# 2016_AdvBeacon.net
KiCad netlist of a schematic drawn in Altium Designer
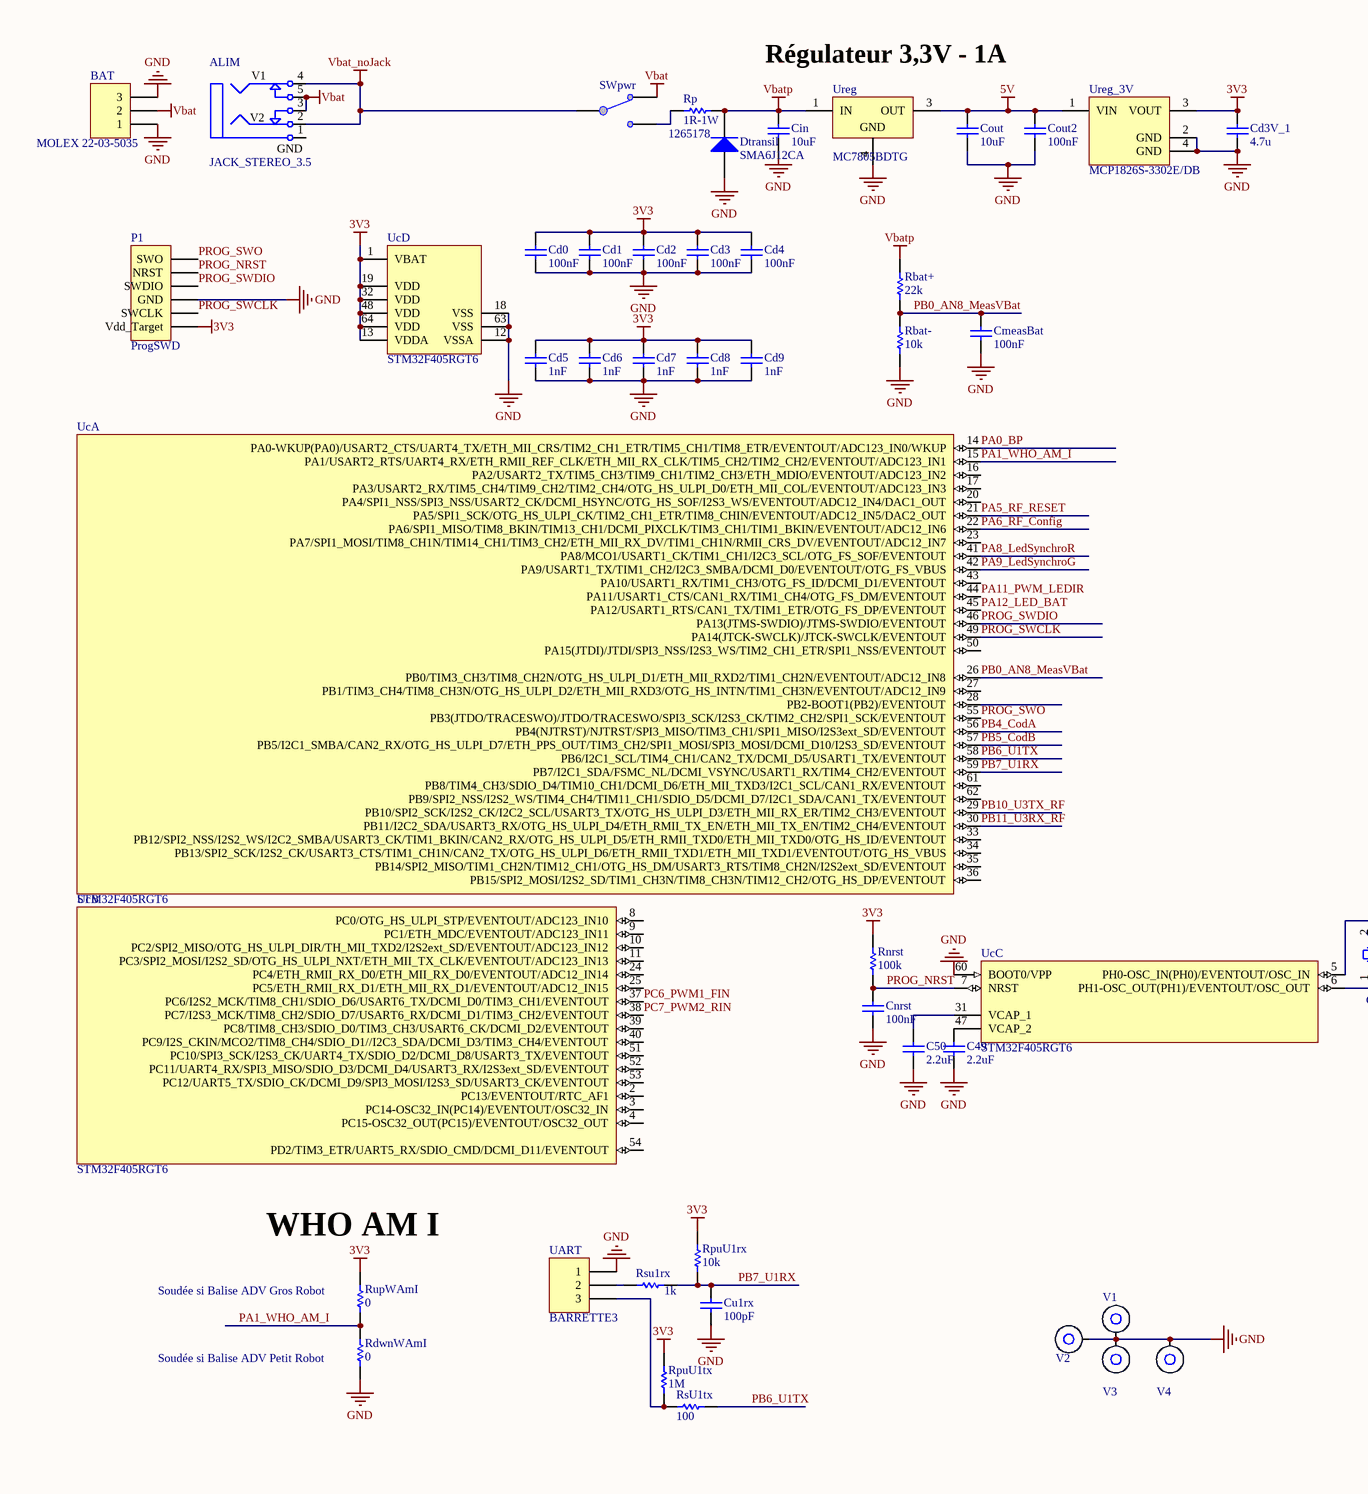
[diagram p0: 2016_AdvBeacon.SchDoc, left]
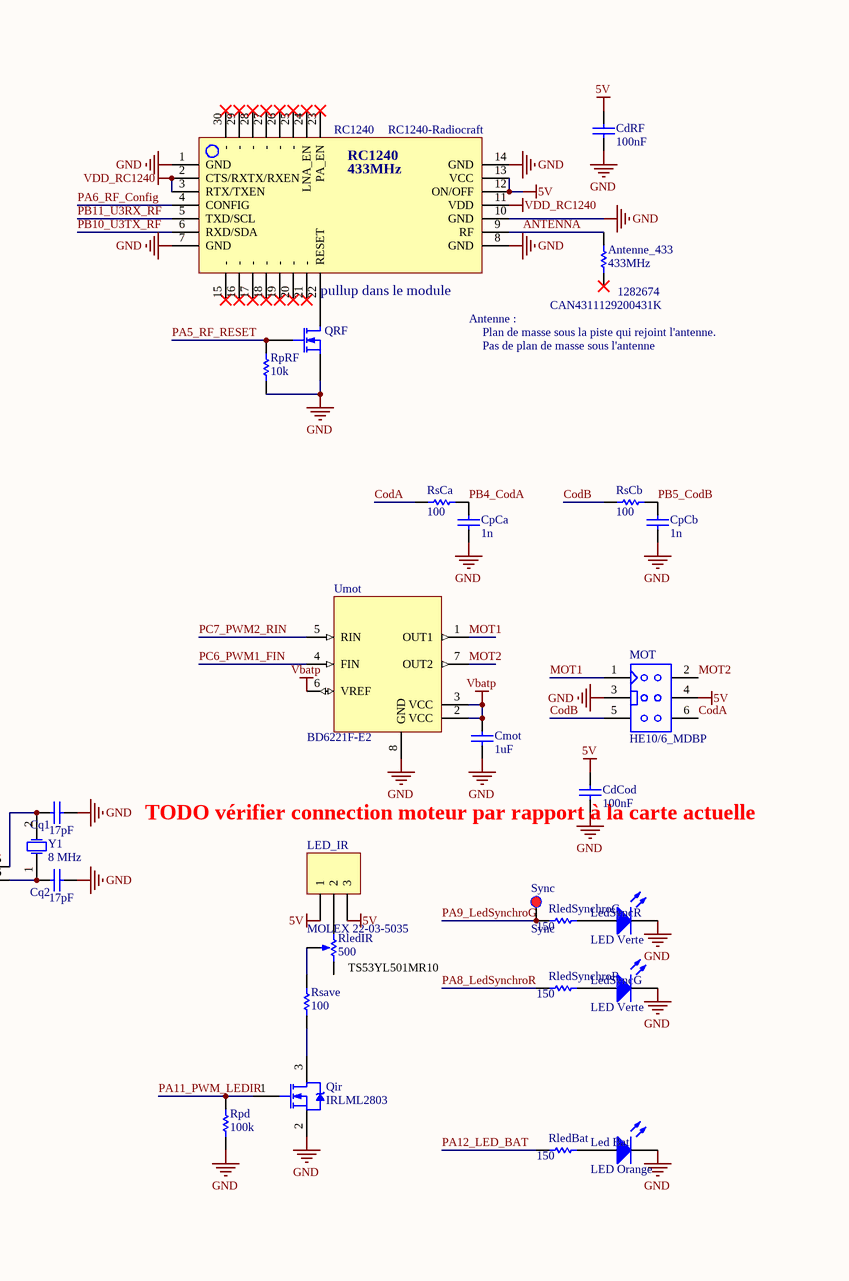
[diagram p1: 2016_AdvBeacon.SchDoc, middle]
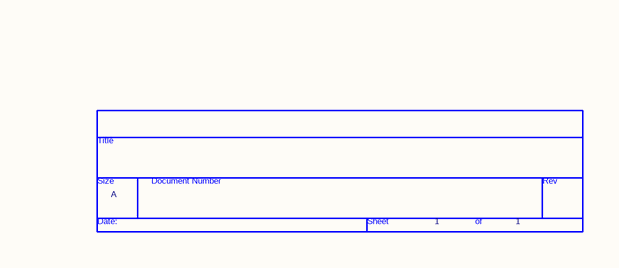
[diagram p2: 2016_AdvBeacon.SchDoc, right]

(export (version "E")
  (design (tool "Eeschema 10.0.6"))
  (components
    (comp (ref "*")
      (value "TitleBlock0")
      (fields (field (name "PAGE COUNT") "1") (field (name "PAGE NUMBER") "1") (field (name "PAGE SIZE") "A"))
      (libsource (lib "*") (part "TitleBlock0"))
    )
    (comp (ref "ALIM")
      (value "EMBASE_JACK_STEREO_3.5mm")
      (footprint "EMBASE_JACK_STEREO_3.5 mm")
      (description "EMBASE JACK STEREO 3.5mm")
      (fields (field (name "TYPE") "JACK_STEREO_3.5"))
      (libsource (lib "connecteurs") (part "EMBASE_JACK_STEREO_3.5mm"))
    )
    (comp (ref "Antenne_433")
      (value "433MHz")
      (footprint "R1206_N")
      (description "CAN4311129200431K")
      (fields
        (field (name "PACKAGEREFERENCE") "CAN4311129200431K")
        (field (name "FAR") "1282674")
        (field (name "PUBLISHER") "Altium Limited")
      )
      (libsource (lib "_ROBOT") (part "Resistor"))
    )
    (comp (ref "BAT")
      (value "MOLEX 22-03-5035")
      (footprint "MOLEX3_2.5MM")
      (description "Header, 3-Pin")
      (fields (field (name "PUBLISHER") "Altium Limited"))
      (libsource (lib "") (part "BARRETTE3_1"))
    )
    (comp (ref "C49")
      (value "2.2uF")
      (footprint "C0805_N")
      (description "Capacitor")
      (fields (field (name "PUBLISHER") "Altium Limited"))
      (libsource (lib "_ROBOT") (part "Condensateur"))
    )
    (comp (ref "C50")
      (value "2.2uF")
      (footprint "C0805_N")
      (description "Capacitor")
      (fields (field (name "PUBLISHER") "Altium Limited"))
      (libsource (lib "_ROBOT") (part "Condensateur"))
    )
    (comp (ref "Cd0")
      (value "100nF")
      (footprint "C0805_N")
      (description "Capacitor")
      (fields (field (name "PUBLISHER") "Altium Limited"))
      (libsource (lib "_ROBOT") (part "Condensateur"))
    )
    (comp (ref "Cd1")
      (value "100nF")
      (footprint "C0805_N")
      (description "Capacitor")
      (fields (field (name "PUBLISHER") "Altium Limited"))
      (libsource (lib "_ROBOT") (part "Condensateur"))
    )
    (comp (ref "Cd2")
      (value "100nF")
      (footprint "C0805_N")
      (description "Capacitor")
      (fields (field (name "PUBLISHER") "Altium Limited"))
      (libsource (lib "_ROBOT") (part "Condensateur"))
    )
    (comp (ref "Cd3")
      (value "100nF")
      (footprint "C0805_N")
      (description "Capacitor")
      (fields (field (name "PUBLISHER") "Altium Limited"))
      (libsource (lib "_ROBOT") (part "Condensateur"))
    )
    (comp (ref "Cd3V_1")
      (value "4.7u")
      (footprint "C0805_N")
      (description "Capacitor")
      (fields (field (name "PUBLISHER") "Altium Limited"))
      (libsource (lib "DG_Condensateur") (part "Capacitor"))
    )
    (comp (ref "Cd4")
      (value "100nF")
      (footprint "C0805_N")
      (description "Capacitor")
      (fields (field (name "PUBLISHER") "Altium Limited"))
      (libsource (lib "_ROBOT") (part "Condensateur"))
    )
    (comp (ref "Cd5")
      (value "1nF")
      (footprint "C0805_N")
      (description "Capacitor")
      (fields (field (name "PUBLISHER") "Altium Limited"))
      (libsource (lib "_ROBOT") (part "Condensateur"))
    )
    (comp (ref "Cd6")
      (value "1nF")
      (footprint "C0805_N")
      (description "Capacitor")
      (fields (field (name "PUBLISHER") "Altium Limited"))
      (libsource (lib "_ROBOT") (part "Condensateur"))
    )
    (comp (ref "Cd7")
      (value "1nF")
      (footprint "C0805_N")
      (description "Capacitor")
      (fields (field (name "PUBLISHER") "Altium Limited"))
      (libsource (lib "_ROBOT") (part "Condensateur"))
    )
    (comp (ref "Cd8")
      (value "1nF")
      (footprint "C0805_N")
      (description "Capacitor")
      (fields (field (name "PUBLISHER") "Altium Limited"))
      (libsource (lib "_ROBOT") (part "Condensateur"))
    )
    (comp (ref "Cd9")
      (value "1nF")
      (footprint "C0805_N")
      (description "Capacitor")
      (fields (field (name "PUBLISHER") "Altium Limited"))
      (libsource (lib "_ROBOT") (part "Condensateur"))
    )
    (comp (ref "CdCod")
      (value "100nF")
      (footprint "C0805_N")
      (description "Capacitor")
      (fields (field (name "PUBLISHER") "Altium Limited"))
      (libsource (lib "DG_Condensateur") (part "Capacitor"))
    )
    (comp (ref "CdRF")
      (value "100nF")
      (footprint "C0805_N")
      (description "Capacitor")
      (fields (field (name "PUBLISHER") "Altium Limited"))
      (libsource (lib "DG_Condensateur") (part "Capacitor"))
    )
    (comp (ref "Cin")
      (value "10uF")
      (footprint "C1206_N")
      (description "Capacitor")
      (fields (field (name "PUBLISHER") "Altium Limited"))
      (libsource (lib "DG_Condensateur") (part "Capacitor"))
    )
    (comp (ref "CmeasBat")
      (value "100nF")
      (footprint "C0805_N")
      (description "Capacitor")
      (fields (field (name "PUBLISHER") "Altium Limited"))
      (libsource (lib "DG_Condensateur") (part "Capacitor"))
    )
    (comp (ref "Cmot")
      (value "1uF")
      (footprint "C1206_N")
      (description "Capacitor")
      (fields (field (name "PUBLISHER") "Altium Limited"))
      (libsource (lib "_ROBOT") (part "Condensateur"))
    )
    (comp (ref "Cnrst")
      (value "100nF")
      (footprint "C0805_N")
      (description "Capacitor")
      (fields (field (name "PUBLISHER") "Altium Limited"))
      (libsource (lib "_ROBOT") (part "Condensateur"))
    )
    (comp (ref "Cout")
      (value "10uF")
      (footprint "C1206_N")
      (description "Capacitor")
      (fields (field (name "PUBLISHER") "Altium Limited"))
      (libsource (lib "DG_Condensateur") (part "Capacitor"))
    )
    (comp (ref "Cout2")
      (value "100nF")
      (footprint "C0805_N")
      (description "Capacitor")
      (fields (field (name "PUBLISHER") "Altium Limited"))
      (libsource (lib "DG_Condensateur") (part "Capacitor"))
    )
    (comp (ref "CpCa")
      (value "1n")
      (footprint "C0805_N")
      (description "Capacitor")
      (fields (field (name "PUBLISHER") "Altium Limited"))
      (libsource (lib "_ROBOT") (part "Condensateur"))
    )
    (comp (ref "CpCb")
      (value "1n")
      (footprint "C0805_N")
      (description "Capacitor")
      (fields (field (name "PUBLISHER") "Altium Limited"))
      (libsource (lib "_ROBOT") (part "Condensateur"))
    )
    (comp (ref "Cq1")
      (value "17pF")
      (footprint "C0805_N")
      (description "Capacitor")
      (fields (field (name "PUBLISHER") "Altium Limited"))
      (libsource (lib "_ROBOT") (part "Condensateur"))
    )
    (comp (ref "Cq2")
      (value "17pF")
      (footprint "C0805_N")
      (description "Capacitor")
      (fields (field (name "PUBLISHER") "Altium Limited"))
      (libsource (lib "_ROBOT") (part "Condensateur"))
    )
    (comp (ref "Cu1rx")
      (value "100pF")
      (footprint "C0805_N")
      (description "Capacitor")
      (fields (field (name "PUBLISHER") "Altium Limited"))
      (libsource (lib "_ROBOT") (part "Condensateur"))
    )
    (comp (ref "Dtransil")
      (value "SMA6J12CA")
      (footprint "DO214AC")
      (description "1 Amp General Purpose Rectifier")
      (fields (field (name "PUBLISHER") "Altium Limited"))
      (libsource (lib "Miscellaneous Devices") (part "Diode 1N4001"))
    )
    (comp (ref "Led Bat")
      (value "LED Orange")
      (footprint "LED_sideView_1204")
      (description "Typical LED")
      (fields (field (name "PUBLISHER") "Altium Limited"))
      (libsource (lib "DG_LED") (part "LED"))
    )
    (comp (ref "LedSyncG")
      (value "LED Verte")
      (footprint "LED_sideView_1204")
      (description "Typical LED")
      (fields (field (name "PUBLISHER") "Altium Limited"))
      (libsource (lib "DG_LED") (part "LED"))
    )
    (comp (ref "LedSyncR")
      (value "LED Verte")
      (footprint "LED_sideView_1204")
      (description "Typical LED")
      (fields (field (name "PUBLISHER") "Altium Limited"))
      (libsource (lib "DG_LED") (part "LED"))
    )
    (comp (ref "LED_IR")
      (value "MOLEX 22-03-5035")
      (footprint "MOLEX3_2.5MM")
      (description "Header, 3-Pin")
      (fields (field (name "PUBLISHER") "Altium Limited"))
      (libsource (lib "") (part "BARRETTE3_2"))
    )
    (comp (ref "MOT")
      (value "HE10/6_MALE_DROIT_BAS PROFIL")
      (footprint "HE10/6_M_D_BP")
      (description "EMBASE HE10/6 MALE DROIT BAS PROFIL")
      (fields (field (name "TYPE") "HE10/6_MDBP"))
      (libsource (lib "connecteurs") (part "HE10/6_MALE_DROIT_BAS PROFIL"))
    )
    (comp (ref "P1")
      (value "ProgSWD")
      (footprint "HDR1X6")
      (description "Header, 6-Pin")
      (fields (field (name "PUBLISHER") "Altium Limited"))
      (libsource (lib "DG_Connecteur") (part "Header 6"))
    )
    (comp (ref "Qir")
      (value "IRLML2803")
      (footprint "SOT23_N")
      (description "HEXFET Power MOSFET")
      (fields (field (name "PUBLISHER") "Altium Limited"))
      (libsource (lib "IR Discrete MOSFET - Power") (part "IRLML2803"))
    )
    (comp (ref "QRF")
      (value "Transistor MOSFET-N")
      (footprint "SOT23-3N")
      (description "N-Channel MOSFET")
      (fields (field (name "PUBLISHER") "Altium Limited"))
      (libsource (lib "_ROBOT") (part "Transistor MOSFET-N"))
    )
    (comp (ref "Rbat+")
      (value "22k")
      (footprint "R1206_N")
      (description "Resistor")
      (fields (field (name "PUBLISHER") "Altium Limited"))
      (libsource (lib "_ROBOT") (part "Resistor"))
    )
    (comp (ref "Rbat-")
      (value "10k")
      (footprint "R1206_N")
      (description "Resistor")
      (fields (field (name "PUBLISHER") "Altium Limited"))
      (libsource (lib "_ROBOT") (part "Resistor"))
    )
    (comp (ref "RC1240")
      (value "RC1240-Radiocraft")
      (footprint "RC1240")
      (description "RC1240 - Radiocraft 433MHz Transceiver")
      (libsource (lib "_ROBOT") (part "RC1240-Radiocraft"))
    )
    (comp (ref "RdwnWAmI")
      (value "0")
      (footprint "R1206_N")
      (description "Resistor")
      (fields (field (name "PUBLISHER") "Altium Limited"))
      (libsource (lib "_ROBOT") (part "Resistor"))
    )
    (comp (ref "RledBat")
      (value "150")
      (footprint "R1206_N")
      (description "Resistor")
      (fields (field (name "PUBLISHER") "Altium Limited"))
      (libsource (lib "_ROBOT") (part "Resistor"))
    )
    (comp (ref "RledIR")
      (value "500")
      (footprint "TRIMMER_CMS_TS53YL")
      (description "Trimmer monotour, Bourns,serie 3314P")
      (libsource (lib "DG_Resistance") (part "Trimmer monotour, Bourns,serie 3314P"))
    )
    (comp (ref "RledSynchroG")
      (value "150")
      (footprint "R1206_N")
      (description "Resistor")
      (fields (field (name "PUBLISHER") "Altium Limited"))
      (libsource (lib "_ROBOT") (part "Resistor"))
    )
    (comp (ref "RledSynchroR")
      (value "150")
      (footprint "R1206_N")
      (description "Resistor")
      (fields (field (name "PUBLISHER") "Altium Limited"))
      (libsource (lib "_ROBOT") (part "Resistor"))
    )
    (comp (ref "Rnrst")
      (value "100k")
      (footprint "R1206_N")
      (description "Resistor")
      (fields (field (name "PUBLISHER") "Altium Limited"))
      (libsource (lib "_ROBOT") (part "Resistor"))
    )
    (comp (ref "Rp")
      (value "1R-1W")
      (footprint "INDUCTANCE_CMS_1812")
      (description "Resistor")
      (fields (field (name "FAR") "1265178") (field (name "PUBLISHER") "Altium Limited"))
      (libsource (lib "_ROBOT") (part "Resistor"))
    )
    (comp (ref "Rpd")
      (value "100k")
      (footprint "R1206_N")
      (description "Resistor")
      (fields (field (name "PUBLISHER") "Altium Limited"))
      (libsource (lib "_ROBOT") (part "Resistor"))
    )
    (comp (ref "RpRF")
      (value "10k")
      (footprint "R1206_N")
      (description "Resistor")
      (fields (field (name "PUBLISHER") "Altium Limited"))
      (libsource (lib "_ROBOT") (part "Resistor"))
    )
    (comp (ref "RpuU1rx")
      (value "10k")
      (footprint "R1206_N")
      (description "Resistor")
      (fields (field (name "PUBLISHER") "Altium Limited"))
      (libsource (lib "_ROBOT") (part "Resistor"))
    )
    (comp (ref "RpuU1tx")
      (value "1M")
      (footprint "R1206_N")
      (description "Resistor")
      (fields (field (name "PUBLISHER") "Altium Limited"))
      (libsource (lib "_ROBOT") (part "Resistor"))
    )
    (comp (ref "Rsave")
      (value "100")
      (footprint "R1206_N")
      (description "Resistor")
      (fields (field (name "PUBLISHER") "Altium Limited"))
      (libsource (lib "_ROBOT") (part "Resistor"))
    )
    (comp (ref "RsCa")
      (value "100")
      (footprint "R1206_N")
      (description "Resistor")
      (fields (field (name "PUBLISHER") "Altium Limited"))
      (libsource (lib "_ROBOT") (part "Resistor"))
    )
    (comp (ref "RsCb")
      (value "100")
      (footprint "R1206_N")
      (description "Resistor")
      (fields (field (name "PUBLISHER") "Altium Limited"))
      (libsource (lib "_ROBOT") (part "Resistor"))
    )
    (comp (ref "Rsu1rx")
      (value "1k")
      (footprint "R1206_N")
      (description "Resistor")
      (fields (field (name "PUBLISHER") "Altium Limited"))
      (libsource (lib "_ROBOT") (part "Resistor"))
    )
    (comp (ref "RsU1tx")
      (value "100")
      (footprint "R1206_N")
      (description "Resistor")
      (fields (field (name "PUBLISHER") "Altium Limited"))
      (libsource (lib "_ROBOT") (part "Resistor"))
    )
    (comp (ref "RupWAmI")
      (value "0")
      (footprint "R1206_N")
      (description "Resistor")
      (fields (field (name "PUBLISHER") "Altium Limited"))
      (libsource (lib "_ROBOT") (part "Resistor"))
    )
    (comp (ref "SWpwr")
      (value "SW SPDT- APEM Série 523x")
      (footprint "SW_UNIPOL_DROIT - Ebay - SPDT - 11x6x5")
      (description "Switch unipolaire a levier")
      (libsource (lib "_ROBOT") (part "SW SPDT- APEM Série 523x"))
    )
    (comp (ref "Sync")
      (value "Sync")
      (footprint "Point Test_D0.9_P0.5mm")
      (description "Point test")
      (fields (field (name "PUBLISHER") "Damien GUITTON"))
      (libsource (lib "Connecteur") (part "Point Test"))
    )
    (comp (ref "UART")
      (value "BARRETTE3")
      (footprint "HDR1X3")
      (description "Header, 3-Pin")
      (fields (field (name "PUBLISHER") "Altium Limited"))
      (libsource (lib "Connecteur") (part "BARRETTE3"))
    )
    (comp (ref "Uc")
      (value "STM32F405RGT6")
      (footprint "TQFP64_V")
      (libsource (lib "STMicroelectronics+STM32+F4") (part "STM32F405RGT6"))
    )
    (comp (ref "Umot")
      (value "BD6221F-E2")
      (footprint "SO8_N")
      (description "H Bridge - 2A")
      (libsource (lib "Circuit intégré") (part "BD6220F"))
    )
    (comp (ref "Ureg")
      (value "MC7805BDTG")
      (footprint "369A-13")
      (description "Three-Terminal Positive Voltage Regulator")
      (fields (field (name "PUBLISHER") "Altium Limited"))
      (libsource (lib "ON Semi Power Mgt Voltage Regulator") (part "MC7805ACD2T"))
    )
    (comp (ref "Ureg_3V")
      (value "MCP1826S-3302E/DB")
      (footprint "SOT223-4N")
      (description "1000 mA, Low Voltage, Low Quiescent Current LDO Regulator, 3-Pin SOT-223, Extended Temperature")
      (fields (field (name "PUBLISHER") "Altium Limited"))
      (libsource (lib "Microchip Power Mgt Line Regulator") (part "MCP1826S-3302E/DB"))
    )
    (comp (ref "V1")
      (value "Entretoise WURTH CMS")
      (footprint "ENTRETOISE_CMS_DOUBLE")
      (description "Entretoise Wurth")
      (fields (field (name "PUBLISHER") "Damien Guitton"))
      (libsource (lib "_ROBOT") (part "Entretoise WURTH CMS_DOUBLE"))
    )
    (comp (ref "V2")
      (value "Entretoise WURTH CMS")
      (footprint "ENTRETOISE_CMS_DOUBLE")
      (description "Entretoise Wurth")
      (fields (field (name "PUBLISHER") "Damien Guitton"))
      (libsource (lib "_ROBOT") (part "Entretoise WURTH CMS_DOUBLE"))
    )
    (comp (ref "V3")
      (value "Entretoise WURTH CMS")
      (footprint "ENTRETOISE_CMS_DOUBLE")
      (description "Entretoise Wurth")
      (fields (field (name "PUBLISHER") "Damien Guitton"))
      (libsource (lib "_ROBOT") (part "Entretoise WURTH CMS_DOUBLE"))
    )
    (comp (ref "V4")
      (value "Entretoise WURTH CMS")
      (footprint "ENTRETOISE_CMS_DOUBLE")
      (description "Entretoise Wurth")
      (fields (field (name "PUBLISHER") "Damien Guitton"))
      (libsource (lib "_ROBOT") (part "Entretoise WURTH CMS_DOUBLE"))
    )
    (comp (ref "Y1")
      (value "8 MHz")
      (footprint "HC49/4H_SMX")
      (description "Crystal Oscillator")
      (fields (field (name "PUBLISHER") "Altium Limited"))
      (libsource (lib "_ROBOT") (part "Quartz"))
    )
  )
  (nets
    (net (code "1") (name "/ANTENNA") (class "Default")
      (node (ref "Antenne_433") (pin "1") (pinfunction "1_1") (pintype "passive"))
      (node (ref "RC1240") (pin "9") (pinfunction "RF_9") (pintype "passive"))
    )
    (net (code "2") (name "/CodA") (class "Default")
      (node (ref "MOT") (pin "6") (pinfunction "6_6") (pintype "passive"))
      (node (ref "RsCa") (pin "2") (pinfunction "2_2") (pintype "passive"))
    )
    (net (code "3") (name "/CodB") (class "Default")
      (node (ref "MOT") (pin "5") (pinfunction "5_5") (pintype "passive"))
      (node (ref "RsCb") (pin "2") (pinfunction "2_2") (pintype "passive"))
    )
    (net (code "4") (name "/MOT1") (class "Default")
      (node (ref "MOT") (pin "1") (pinfunction "1_1") (pintype "passive"))
      (node (ref "Umot") (pin "1") (pinfunction "OUT1_1") (pintype "output"))
    )
    (net (code "5") (name "/MOT2") (class "Default")
      (node (ref "MOT") (pin "2") (pinfunction "2_2") (pintype "passive"))
      (node (ref "Umot") (pin "7") (pinfunction "OUT2_7") (pintype "output"))
    )
    (net (code "6") (name "/PA0_BP") (class "Default")
      (node (ref "Uc") (pin "14") (pinfunction "PA0-WKUP(PA0)/USART2_CTS/UART4_TX/ETH_MII_CRS/TIM2_CH1_ETR/TIM5_CH1/TIM8_ETR/EVENTOUT/ADC123_IN0/WKUP_14") (pintype "bidirectional"))
    )
    (net (code "7") (name "/PA1_WHO_AM_I") (class "Default")
      (node (ref "RdwnWAmI") (pin "2") (pinfunction "2_2") (pintype "passive"))
      (node (ref "RupWAmI") (pin "1") (pinfunction "1_1") (pintype "passive"))
      (node (ref "Uc") (pin "15") (pinfunction "PA1/USART2_RTS/UART4_RX/ETH_RMII_REF_CLK/ETH_MII_RX_CLK/TIM5_CH2/TIM2_CH2/EVENTOUT/ADC123_IN1_15") (pintype "bidirectional"))
    )
    (net (code "8") (name "/PA5_RF_RESET") (class "Default")
      (node (ref "QRF") (pin "1") (pinfunction "G_1") (pintype "passive"))
      (node (ref "RpRF") (pin "1") (pinfunction "1_1") (pintype "passive"))
      (node (ref "Uc") (pin "21") (pinfunction "PA5/SPI1_SCK/OTG_HS_ULPI_CK/TIM2_CH1_ETR/TIM8_CHIN/EVENTOUT/ADC12_IN5/DAC2_OUT_21") (pintype "bidirectional"))
    )
    (net (code "9") (name "/PA6_RF_Config") (class "Default")
      (node (ref "RC1240") (pin "4") (pinfunction "CONFIG_4") (pintype "passive"))
      (node (ref "Uc") (pin "22") (pinfunction "PA6/SPI1_MISO/TIM8_BKIN/TIM13_CH1/DCMI_PIXCLK/TIM3_CH1/TIM1_BKIN/EVENTOUT/ADC12_IN6_22") (pintype "bidirectional"))
    )
    (net (code "10") (name "/PA8_LedSynchroR") (class "Default")
      (node (ref "RledSynchroR") (pin "2") (pinfunction "2_2") (pintype "passive"))
      (node (ref "Uc") (pin "41") (pinfunction "PA8/MCO1/USART1_CK/TIM1_CH1/I2C3_SCL/OTG_FS_SOF/EVENTOUT_41") (pintype "bidirectional"))
    )
    (net (code "11") (name "/PA9_LedSynchroG") (class "Default")
      (node (ref "RledSynchroG") (pin "2") (pinfunction "2_2") (pintype "passive"))
      (node (ref "Sync") (pin "1") (pinfunction "1_1") (pintype "passive"))
      (node (ref "Uc") (pin "42") (pinfunction "PA9/USART1_TX/TIM1_CH2/I2C3_SMBA/DCMI_D0/EVENTOUT/OTG_FS_VBUS_42") (pintype "bidirectional"))
    )
    (net (code "12") (name "/PA11_PWM_LEDIR") (class "Default")
      (node (ref "Qir") (pin "1") (pinfunction "G_1") (pintype "passive"))
      (node (ref "Rpd") (pin "2") (pinfunction "2_2") (pintype "passive"))
      (node (ref "Uc") (pin "44") (pinfunction "PA11/USART1_CTS/CAN1_RX/TIM1_CH4/OTG_FS_DM/EVENTOUT_44") (pintype "bidirectional"))
    )
    (net (code "13") (name "/PA12_LED_BAT") (class "Default")
      (node (ref "RledBat") (pin "2") (pinfunction "2_2") (pintype "passive"))
      (node (ref "Uc") (pin "45") (pinfunction "PA12/USART1_RTS/CAN1_TX/TIM1_ETR/OTG_FS_DP/EVENTOUT_45") (pintype "bidirectional"))
    )
    (net (code "14") (name "/PB0_AN8_MeasVBat") (class "Default")
      (node (ref "CmeasBat") (pin "2") (pinfunction "2_2") (pintype "passive"))
      (node (ref "Rbat+") (pin "2") (pinfunction "2_2") (pintype "passive"))
      (node (ref "Rbat-") (pin "1") (pinfunction "1_1") (pintype "passive"))
      (node (ref "Uc") (pin "26") (pinfunction "PB0/TIM3_CH3/TIM8_CH2N/OTG_HS_ULPI_D1/ETH_MII_RXD2/TIM1_CH2N/EVENTOUT/ADC12_IN8_26") (pintype "bidirectional"))
    )
    (net (code "15") (name "/PB4_CodA") (class "Default")
      (node (ref "CpCa") (pin "1") (pinfunction "1_1") (pintype "passive"))
      (node (ref "RsCa") (pin "1") (pinfunction "1_1") (pintype "passive"))
      (node (ref "Uc") (pin "56") (pinfunction "PB4(NJTRST)/NJTRST/SPI3_MISO/TIM3_CH1/SPI1_MISO/I2S3ext_SD/EVENTOUT_56") (pintype "bidirectional"))
    )
    (net (code "16") (name "/PB5_CodB") (class "Default")
      (node (ref "CpCb") (pin "1") (pinfunction "1_1") (pintype "passive"))
      (node (ref "RsCb") (pin "1") (pinfunction "1_1") (pintype "passive"))
      (node (ref "Uc") (pin "57") (pinfunction "PB5/I2C1_SMBA/CAN2_RX/OTG_HS_ULPI_D7/ETH_PPS_OUT/TIM3_CH2/SPI1_MOSI/SPI3_MOSI/DCMI_D10/I2S3_SD/EVENTOUT_57") (pintype "bidirectional"))
    )
    (net (code "17") (name "/PB6_U1TX") (class "Default")
      (node (ref "RsU1tx") (pin "2") (pinfunction "2_2") (pintype "passive"))
      (node (ref "Uc") (pin "58") (pinfunction "PB6/I2C1_SCL/TIM4_CH1/CAN2_TX/DCMI_D5/USART1_TX/EVENTOUT_58") (pintype "bidirectional"))
    )
    (net (code "18") (name "/PB7_U1RX") (class "Default")
      (node (ref "Cu1rx") (pin "2") (pinfunction "2_2") (pintype "passive"))
      (node (ref "RpuU1rx") (pin "1") (pinfunction "1_1") (pintype "passive"))
      (node (ref "Rsu1rx") (pin "1") (pinfunction "1_1") (pintype "passive"))
      (node (ref "Uc") (pin "59") (pinfunction "PB7/I2C1_SDA/FSMC_NL/DCMI_VSYNC/USART1_RX/TIM4_CH2/EVENTOUT_59") (pintype "bidirectional"))
    )
    (net (code "19") (name "/PB10_U3TX_RF") (class "Default")
      (node (ref "RC1240") (pin "6") (pinfunction "RXD/SDA_6") (pintype "passive"))
      (node (ref "Uc") (pin "29") (pinfunction "PB10/SPI2_SCK/I2S2_CK/I2C2_SCL/USART3_TX/OTG_HS_ULPI_D3/ETH_MII_RX_ER/TIM2_CH3/EVENTOUT_29") (pintype "bidirectional"))
    )
    (net (code "20") (name "/PB11_U3RX_RF") (class "Default")
      (node (ref "RC1240") (pin "5") (pinfunction "TXD/SCL_5") (pintype "passive"))
      (node (ref "Uc") (pin "30") (pinfunction "PB11/I2C2_SDA/USART3_RX/OTG_HS_ULPI_D4/ETH_RMII_TX_EN/ETH_MII_TX_EN/TIM2_CH4/EVENTOUT_30") (pintype "bidirectional"))
    )
    (net (code "21") (name "/PC6_PWM1_FIN") (class "Default")
      (node (ref "Uc") (pin "37") (pinfunction "PC6/I2S2_MCK/TIM8_CH1/SDIO_D6/USART6_TX/DCMI_D0/TIM3_CH1/EVENTOUT_37") (pintype "bidirectional"))
      (node (ref "Umot") (pin "4") (pinfunction "FIN_4") (pintype "input"))
    )
    (net (code "22") (name "/PC7_PWM2_RIN") (class "Default")
      (node (ref "Uc") (pin "38") (pinfunction "PC7/I2S3_MCK/TIM8_CH2/SDIO_D7/USART6_RX/DCMI_D1/TIM3_CH2/EVENTOUT_38") (pintype "bidirectional"))
      (node (ref "Umot") (pin "5") (pinfunction "RIN_5") (pintype "input"))
    )
    (net (code "23") (name "/PROG_NRST") (class "Default")
      (node (ref "Cnrst") (pin "2") (pinfunction "2_2") (pintype "passive"))
      (node (ref "P1") (pin "5") (pinfunction "NRST_5") (pintype "passive"))
      (node (ref "Rnrst") (pin "1") (pinfunction "1_1") (pintype "passive"))
      (node (ref "Uc") (pin "7") (pinfunction "NRST_7") (pintype "bidirectional"))
    )
    (net (code "24") (name "/PROG_SWCLK") (class "Default")
      (node (ref "P1") (pin "2") (pinfunction "SWCLK_2") (pintype "passive"))
      (node (ref "Uc") (pin "49") (pinfunction "PA14(JTCK-SWCLK)/JTCK-SWCLK/EVENTOUT_49") (pintype "bidirectional"))
    )
    (net (code "25") (name "/PROG_SWDIO") (class "Default")
      (node (ref "P1") (pin "4") (pinfunction "SWDIO_4") (pintype "passive"))
      (node (ref "Uc") (pin "46") (pinfunction "PA13(JTMS-SWDIO)/JTMS-SWDIO/EVENTOUT_46") (pintype "bidirectional"))
    )
    (net (code "26") (name "/PROG_SWO") (class "Default")
      (node (ref "P1") (pin "6") (pinfunction "SWO_6") (pintype "passive"))
      (node (ref "Uc") (pin "55") (pinfunction "PB3(JTDO/TRACESWO)/JTDO/TRACESWO/SPI3_SCK/I2S3_CK/TIM2_CH2/SPI1_SCK/EVENTOUT_55") (pintype "bidirectional"))
    )
    (net (code "27") (name "3V3") (class "Default")
      (node (ref "Cd0") (pin "2") (pinfunction "2_2") (pintype "passive"))
      (node (ref "Cd1") (pin "2") (pinfunction "2_2") (pintype "passive"))
      (node (ref "Cd2") (pin "2") (pinfunction "2_2") (pintype "passive"))
      (node (ref "Cd3") (pin "2") (pinfunction "2_2") (pintype "passive"))
      (node (ref "Cd3V_1") (pin "2") (pinfunction "2_2") (pintype "passive"))
      (node (ref "Cd4") (pin "2") (pinfunction "2_2") (pintype "passive"))
      (node (ref "Cd5") (pin "2") (pinfunction "2_2") (pintype "passive"))
      (node (ref "Cd6") (pin "2") (pinfunction "2_2") (pintype "passive"))
      (node (ref "Cd7") (pin "2") (pinfunction "2_2") (pintype "passive"))
      (node (ref "Cd8") (pin "2") (pinfunction "2_2") (pintype "passive"))
      (node (ref "Cd9") (pin "2") (pinfunction "2_2") (pintype "passive"))
      (node (ref "P1") (pin "1") (pinfunction "Vdd_Target_1") (pintype "passive"))
      (node (ref "Rnrst") (pin "2") (pinfunction "2_2") (pintype "passive"))
      (node (ref "RpuU1rx") (pin "2") (pinfunction "2_2") (pintype "passive"))
      (node (ref "RpuU1tx") (pin "2") (pinfunction "2_2") (pintype "passive"))
      (node (ref "RupWAmI") (pin "2") (pinfunction "2_2") (pintype "passive"))
      (node (ref "Uc") (pin "1") (pinfunction "VBAT_1") (pintype "power_in"))
      (node (ref "Uc") (pin "13") (pinfunction "VDDA_13") (pintype "power_in"))
      (node (ref "Uc") (pin "19") (pinfunction "VDD_19") (pintype "power_in"))
      (node (ref "Uc") (pin "32") (pinfunction "VDD_32") (pintype "power_in"))
      (node (ref "Uc") (pin "48") (pinfunction "VDD_48") (pintype "power_in"))
      (node (ref "Uc") (pin "64") (pinfunction "VDD_64") (pintype "power_in"))
      (node (ref "Ureg_3V") (pin "3") (pinfunction "VOUT_3") (pintype "power_in"))
    )
    (net (code "28") (name "5V") (class "Default")
      (node (ref "CdCod") (pin "2") (pinfunction "2_2") (pintype "passive"))
      (node (ref "CdRF") (pin "2") (pinfunction "2_2") (pintype "passive"))
      (node (ref "Cout") (pin "2") (pinfunction "2_2") (pintype "passive"))
      (node (ref "Cout2") (pin "2") (pinfunction "2_2") (pintype "passive"))
      (node (ref "LED_IR") (pin "1") (pinfunction "1_1") (pintype "passive"))
      (node (ref "LED_IR") (pin "3") (pinfunction "3_3") (pintype "passive"))
      (node (ref "MOT") (pin "4") (pinfunction "4_4") (pintype "passive"))
      (node (ref "RC1240") (pin "12") (pinfunction "ON/OFF_12") (pintype "passive"))
      (node (ref "RC1240") (pin "13") (pinfunction "VCC_13") (pintype "passive"))
      (node (ref "Ureg") (pin "3") (pinfunction "OUT_3") (pintype "power_in"))
      (node (ref "Ureg_3V") (pin "1") (pinfunction "VIN_1") (pintype "power_in"))
    )
    (net (code "29") (name "GND") (class "Default")
      (node (ref "BAT") (pin "1") (pinfunction "1_1") (pintype "passive"))
      (node (ref "BAT") (pin "3") (pinfunction "3_3") (pintype "passive"))
      (node (ref "C49") (pin "1") (pinfunction "1_1") (pintype "passive"))
      (node (ref "C50") (pin "1") (pinfunction "1_1") (pintype "passive"))
      (node (ref "Cd0") (pin "1") (pinfunction "1_1") (pintype "passive"))
      (node (ref "Cd1") (pin "1") (pinfunction "1_1") (pintype "passive"))
      (node (ref "Cd2") (pin "1") (pinfunction "1_1") (pintype "passive"))
      (node (ref "Cd3") (pin "1") (pinfunction "1_1") (pintype "passive"))
      (node (ref "Cd3V_1") (pin "1") (pinfunction "1_1") (pintype "passive"))
      (node (ref "Cd4") (pin "1") (pinfunction "1_1") (pintype "passive"))
      (node (ref "Cd5") (pin "1") (pinfunction "1_1") (pintype "passive"))
      (node (ref "Cd6") (pin "1") (pinfunction "1_1") (pintype "passive"))
      (node (ref "Cd7") (pin "1") (pinfunction "1_1") (pintype "passive"))
      (node (ref "Cd8") (pin "1") (pinfunction "1_1") (pintype "passive"))
      (node (ref "Cd9") (pin "1") (pinfunction "1_1") (pintype "passive"))
      (node (ref "CdCod") (pin "1") (pinfunction "1_1") (pintype "passive"))
      (node (ref "CdRF") (pin "1") (pinfunction "1_1") (pintype "passive"))
      (node (ref "Cin") (pin "1") (pinfunction "1_1") (pintype "passive"))
      (node (ref "CmeasBat") (pin "1") (pinfunction "1_1") (pintype "passive"))
      (node (ref "Cmot") (pin "1") (pinfunction "1_1") (pintype "passive"))
      (node (ref "Cnrst") (pin "1") (pinfunction "1_1") (pintype "passive"))
      (node (ref "Cout") (pin "1") (pinfunction "1_1") (pintype "passive"))
      (node (ref "Cout2") (pin "1") (pinfunction "1_1") (pintype "passive"))
      (node (ref "CpCa") (pin "2") (pinfunction "2_2") (pintype "passive"))
      (node (ref "CpCb") (pin "2") (pinfunction "2_2") (pintype "passive"))
      (node (ref "Cq1") (pin "1") (pinfunction "1_1") (pintype "passive"))
      (node (ref "Cq2") (pin "1") (pinfunction "1_1") (pintype "passive"))
      (node (ref "Cu1rx") (pin "1") (pinfunction "1_1") (pintype "passive"))
      (node (ref "Dtransil") (pin "1") (pinfunction "A_1") (pintype "passive"))
      (node (ref "Led Bat") (pin "2") (pinfunction "K_2") (pintype "passive"))
      (node (ref "LedSyncG") (pin "2") (pinfunction "K_2") (pintype "passive"))
      (node (ref "LedSyncR") (pin "2") (pinfunction "K_2") (pintype "passive"))
      (node (ref "MOT") (pin "3") (pinfunction "3_3") (pintype "passive"))
      (node (ref "P1") (pin "3") (pinfunction "GND_3") (pintype "passive"))
      (node (ref "QRF") (pin "2") (pinfunction "S_2") (pintype "passive"))
      (node (ref "Qir") (pin "2") (pinfunction "S_2") (pintype "passive"))
      (node (ref "RC1240") (pin "1") (pinfunction "GND_1") (pintype "passive"))
      (node (ref "RC1240") (pin "10") (pinfunction "GND_10") (pintype "passive"))
      (node (ref "RC1240") (pin "14") (pinfunction "GND_14") (pintype "passive"))
      (node (ref "RC1240") (pin "7") (pinfunction "GND_7") (pintype "passive"))
      (node (ref "RC1240") (pin "8") (pinfunction "GND_8") (pintype "passive"))
      (node (ref "Rbat-") (pin "2") (pinfunction "2_2") (pintype "passive"))
      (node (ref "RdwnWAmI") (pin "1") (pinfunction "1_1") (pintype "passive"))
      (node (ref "RpRF") (pin "2") (pinfunction "2_2") (pintype "passive"))
      (node (ref "Rpd") (pin "1") (pinfunction "1_1") (pintype "passive"))
      (node (ref "UART") (pin "1") (pinfunction "1_1") (pintype "passive"))
      (node (ref "Uc") (pin "12") (pinfunction "VSSA_12") (pintype "power_in"))
      (node (ref "Uc") (pin "18") (pinfunction "VSS_18") (pintype "power_in"))
      (node (ref "Uc") (pin "60") (pinfunction "BOOT0/VPP_60") (pintype "input"))
      (node (ref "Uc") (pin "63") (pinfunction "VSS_63") (pintype "power_in"))
      (node (ref "Umot") (pin "8") (pinfunction "GND_8") (pintype "power_in"))
      (node (ref "Ureg") (pin "4") (pinfunction "GND_4") (pintype "power_in"))
      (node (ref "Ureg_3V") (pin "2") (pinfunction "GND_2") (pintype "power_in"))
      (node (ref "Ureg_3V") (pin "4") (pinfunction "GND_4") (pintype "power_in"))
      (node (ref "V1") (pin "1") (pinfunction "1_1") (pintype "passive"))
      (node (ref "V2") (pin "1") (pinfunction "1_1") (pintype "passive"))
      (node (ref "V3") (pin "1") (pinfunction "1_1") (pintype "passive"))
      (node (ref "V4") (pin "1") (pinfunction "1_1") (pintype "passive"))
    )
    (net (code "30") (name "Net-(Led Bat-A)") (class "Default")
      (node (ref "Led Bat") (pin "1") (pinfunction "A_1") (pintype "passive"))
      (node (ref "RledBat") (pin "1") (pinfunction "1_1") (pintype "passive"))
    )
    (net (code "31") (name "Net-(LedSyncG-A)") (class "Default")
      (node (ref "LedSyncG") (pin "1") (pinfunction "A_1") (pintype "passive"))
      (node (ref "RledSynchroR") (pin "1") (pinfunction "1_1") (pintype "passive"))
    )
    (net (code "32") (name "Net-(LedSyncR-A)") (class "Default")
      (node (ref "LedSyncR") (pin "1") (pinfunction "A_1") (pintype "passive"))
      (node (ref "RledSynchroG") (pin "1") (pinfunction "1_1") (pintype "passive"))
    )
    (net (code "33") (name "Net-(QRF-D)") (class "Default")
      (node (ref "QRF") (pin "3") (pinfunction "D_3") (pintype "passive"))
      (node (ref "RC1240") (pin "22") (pinfunction "RESET_22") (pintype "passive"))
    )
    (net (code "34") (name "Net-(Qir-D)") (class "Default")
      (node (ref "Qir") (pin "3") (pinfunction "D_3") (pintype "passive"))
      (node (ref "Rsave") (pin "1") (pinfunction "1_1") (pintype "passive"))
    )
    (net (code "35") (name "Net-(RledIR-TAP)") (class "Default")
      (node (ref "RledIR") (pin "2") (pinfunction "TAP_2") (pintype "passive"))
      (node (ref "Rsave") (pin "2") (pinfunction "2_2") (pintype "passive"))
    )
    (net (code "36") (name "Net-(RledIR-TOP)") (class "Default")
      (node (ref "LED_IR") (pin "2") (pinfunction "2_2") (pintype "passive"))
      (node (ref "RledIR") (pin "1") (pinfunction "TOP_1") (pintype "passive"))
    )
    (net (code "37") (name "Net-(Rp-Pad1)") (class "Default")
      (node (ref "Rp") (pin "1") (pinfunction "1_1") (pintype "passive"))
      (node (ref "SWpwr") (pin "NO1") (pinfunction "NO1_NO1") (pintype "passive"))
    )
    (net (code "38") (name "Net-(RpuU1tx-Pad1)") (class "Default")
      (node (ref "RpuU1tx") (pin "1") (pinfunction "1_1") (pintype "passive"))
      (node (ref "RsU1tx") (pin "1") (pinfunction "1_1") (pintype "passive"))
      (node (ref "UART") (pin "3") (pinfunction "3_3") (pintype "passive"))
    )
    (net (code "39") (name "Net-(Rsu1rx-Pad2)") (class "Default")
      (node (ref "Rsu1rx") (pin "2") (pinfunction "2_2") (pintype "passive"))
      (node (ref "UART") (pin "2") (pinfunction "2_2") (pintype "passive"))
    )
    (net (code "40") (name "Net-(UcC-PH0-OSC_IN(PH0){slash}EVENTOUT{slash}OSC_IN)") (class "Default")
      (node (ref "Cq1") (pin "2") (pinfunction "2_2") (pintype "passive"))
      (node (ref "Uc") (pin "5") (pinfunction "PH0-OSC_IN(PH0)/EVENTOUT/OSC_IN_5") (pintype "bidirectional"))
      (node (ref "Y1") (pin "2") (pinfunction "OSC2_2") (pintype "passive"))
    )
    (net (code "41") (name "Net-(UcC-PH1-OSC_OUT(PH1){slash}EVENTOUT{slash}OSC_OUT)") (class "Default")
      (node (ref "Cq2") (pin "2") (pinfunction "2_2") (pintype "passive"))
      (node (ref "Uc") (pin "6") (pinfunction "PH1-OSC_OUT(PH1)/EVENTOUT/OSC_OUT_6") (pintype "bidirectional"))
      (node (ref "Y1") (pin "1") (pinfunction "OSC1_1") (pintype "passive"))
    )
    (net (code "42") (name "Net-(UcC-VCAP_1)") (class "Default")
      (node (ref "C50") (pin "2") (pinfunction "2_2") (pintype "passive"))
      (node (ref "Uc") (pin "31") (pinfunction "VCAP_1_31") (pintype "power_in"))
    )
    (net (code "43") (name "Net-(UcC-VCAP_2)") (class "Default")
      (node (ref "C49") (pin "2") (pinfunction "2_2") (pintype "passive"))
      (node (ref "Uc") (pin "47") (pinfunction "VCAP_2_47") (pintype "power_in"))
    )
    (net (code "44") (name "VDD_RC1240") (class "Default")
      (node (ref "RC1240") (pin "11") (pinfunction "VDD_11") (pintype "passive"))
      (node (ref "RC1240") (pin "2") (pinfunction "CTS/RXTX/RXEN_2") (pintype "passive"))
      (node (ref "RC1240") (pin "3") (pinfunction "RTX/TXEN_3") (pintype "passive"))
    )
    (net (code "45") (name "Vbat") (class "Default")
      (node (ref "ALIM") (pin "3") (pinfunction "3_3") (pintype "passive"))
      (node (ref "ALIM") (pin "5") (pinfunction "5_5") (pintype "passive"))
      (node (ref "BAT") (pin "2") (pinfunction "2_2") (pintype "passive"))
      (node (ref "SWpwr") (pin "NC1") (pinfunction "NC1_NC1") (pintype "passive"))
    )
    (net (code "46") (name "Vbat_noJack") (class "Default")
      (node (ref "ALIM") (pin "2") (pinfunction "2_2") (pintype "passive"))
      (node (ref "ALIM") (pin "4") (pinfunction "4_4") (pintype "passive"))
      (node (ref "SWpwr") (pin "COMMON1") (pinfunction "COMMON1_COMMON1") (pintype "passive"))
    )
    (net (code "47") (name "Vbatp") (class "Default")
      (node (ref "Cin") (pin "2") (pinfunction "2_2") (pintype "passive"))
      (node (ref "Cmot") (pin "2") (pinfunction "2_2") (pintype "passive"))
      (node (ref "Dtransil") (pin "2") (pinfunction "K_2") (pintype "passive"))
      (node (ref "Rbat+") (pin "1") (pinfunction "1_1") (pintype "passive"))
      (node (ref "Rp") (pin "2") (pinfunction "2_2") (pintype "passive"))
      (node (ref "Umot") (pin "2") (pinfunction "VCC_2") (pintype "power_in"))
      (node (ref "Umot") (pin "3") (pinfunction "VCC_3") (pintype "power_in"))
      (node (ref "Umot") (pin "6") (pinfunction "VREF_6") (pintype "bidirectional"))
      (node (ref "Ureg") (pin "1") (pinfunction "IN_1") (pintype "power_in"))
    )
    (net (code "48") (name "unconnected-(ALIM-Pad1)") (class "Default")
      (node (ref "ALIM") (pin "1") (pinfunction "1_1") (pintype "passive"))
    )
    (net (code "49") (name "unconnected-(Antenne_433-Pad2)") (class "Default")
      (node (ref "Antenne_433") (pin "2") (pinfunction "2_2") (pintype "passive+no_connect"))
    )
    (net (code "50") (name "unconnected-(RC1240---Pad15)") (class "Default")
      (node (ref "RC1240") (pin "15") (pinfunction "-_15") (pintype "passive+no_connect"))
    )
    (net (code "51") (name "unconnected-(RC1240---Pad16)") (class "Default")
      (node (ref "RC1240") (pin "16") (pinfunction "-_16") (pintype "passive+no_connect"))
    )
    (net (code "52") (name "unconnected-(RC1240---Pad17)") (class "Default")
      (node (ref "RC1240") (pin "17") (pinfunction "-_17") (pintype "passive+no_connect"))
    )
    (net (code "53") (name "unconnected-(RC1240---Pad18)") (class "Default")
      (node (ref "RC1240") (pin "18") (pinfunction "-_18") (pintype "passive+no_connect"))
    )
    (net (code "54") (name "unconnected-(RC1240---Pad19)") (class "Default")
      (node (ref "RC1240") (pin "19") (pinfunction "-_19") (pintype "passive+no_connect"))
    )
    (net (code "55") (name "unconnected-(RC1240---Pad20)") (class "Default")
      (node (ref "RC1240") (pin "20") (pinfunction "-_20") (pintype "passive+no_connect"))
    )
    (net (code "56") (name "unconnected-(RC1240---Pad21)") (class "Default")
      (node (ref "RC1240") (pin "21") (pinfunction "-_21") (pintype "passive+no_connect"))
    )
    (net (code "57") (name "unconnected-(RC1240---Pad25)") (class "Default")
      (node (ref "RC1240") (pin "25") (pinfunction "-_25") (pintype "passive+no_connect"))
    )
    (net (code "58") (name "unconnected-(RC1240---Pad26)") (class "Default")
      (node (ref "RC1240") (pin "26") (pinfunction "-_26") (pintype "passive+no_connect"))
    )
    (net (code "59") (name "unconnected-(RC1240---Pad27)") (class "Default")
      (node (ref "RC1240") (pin "27") (pinfunction "-_27") (pintype "passive+no_connect"))
    )
    (net (code "60") (name "unconnected-(RC1240---Pad28)") (class "Default")
      (node (ref "RC1240") (pin "28") (pinfunction "-_28") (pintype "passive+no_connect"))
    )
    (net (code "61") (name "unconnected-(RC1240---Pad29)") (class "Default")
      (node (ref "RC1240") (pin "29") (pinfunction "-_29") (pintype "passive+no_connect"))
    )
    (net (code "62") (name "unconnected-(RC1240---Pad30)") (class "Default")
      (node (ref "RC1240") (pin "30") (pinfunction "-_30") (pintype "passive+no_connect"))
    )
    (net (code "63") (name "unconnected-(RC1240-LNA_EN-Pad24)") (class "Default")
      (node (ref "RC1240") (pin "24") (pinfunction "LNA_EN_24") (pintype "passive+no_connect"))
    )
    (net (code "64") (name "unconnected-(RC1240-PA_EN-Pad23)") (class "Default")
      (node (ref "RC1240") (pin "23") (pinfunction "PA_EN_23") (pintype "passive+no_connect"))
    )
    (net (code "65") (name "unconnected-(RledIR-BOT-Pad3)") (class "Default")
      (node (ref "RledIR") (pin "3") (pinfunction "BOT_3") (pintype "passive"))
    )
    (net (code "66") (name "unconnected-(UcA-PA2{slash}USART2_TX{slash}TIM5_CH3{slash}TIM9_CH1{slash}TIM2_CH3{slash}ETH_MDIO{slash}EVENTOUT{slash}ADC123_IN2-Pad16)") (class "Default")
      (node (ref "Uc") (pin "16") (pinfunction "PA2/USART2_TX/TIM5_CH3/TIM9_CH1/TIM2_CH3/ETH_MDIO/EVENTOUT/ADC123_IN2_16") (pintype "bidirectional"))
    )
    (net (code "67") (name "unconnected-(UcA-PA3{slash}USART2_RX{slash}TIM5_CH4{slash}TIM9_CH2{slash}TIM2_CH4{slash}OTG_HS_ULPI_D0{slash}ETH_MII_COL{slash}EVENTOUT{slash}ADC123_IN3-Pad17)") (class "Default")
      (node (ref "Uc") (pin "17") (pinfunction "PA3/USART2_RX/TIM5_CH4/TIM9_CH2/TIM2_CH4/OTG_HS_ULPI_D0/ETH_MII_COL/EVENTOUT/ADC123_IN3_17") (pintype "bidirectional"))
    )
    (net (code "68") (name "unconnected-(UcA-PA4{slash}SPI1_NSS{slash}SPI3_NSS{slash}USART2_CK{slash}DCMI_HSYNC{slash}OTG_HS_SOF{slash}I2S3_WS{slash}EVENTOUT{slash}ADC12_IN4{slash}DAC1_OUT-Pad20)") (class "Default")
      (node (ref "Uc") (pin "20") (pinfunction "PA4/SPI1_NSS/SPI3_NSS/USART2_CK/DCMI_HSYNC/OTG_HS_SOF/I2S3_WS/EVENTOUT/ADC12_IN4/DAC1_OUT_20") (pintype "bidirectional"))
    )
    (net (code "69") (name "unconnected-(UcA-PA7{slash}SPI1_MOSI{slash}TIM8_CH1N{slash}TIM14_CH1{slash}TIM3_CH2{slash}ETH_MII_RX_DV{slash}TIM1_CH1N{slash}RMII_CRS_DV{slash}EVENTOUT{slash}ADC12_IN7-Pad23)") (class "Default")
      (node (ref "Uc") (pin "23") (pinfunction "PA7/SPI1_MOSI/TIM8_CH1N/TIM14_CH1/TIM3_CH2/ETH_MII_RX_DV/TIM1_CH1N/RMII_CRS_DV/EVENTOUT/ADC12_IN7_23") (pintype "bidirectional"))
    )
    (net (code "70") (name "unconnected-(UcA-PA10{slash}USART1_RX{slash}TIM1_CH3{slash}OTG_FS_ID{slash}DCMI_D1{slash}EVENTOUT-Pad43)") (class "Default")
      (node (ref "Uc") (pin "43") (pinfunction "PA10/USART1_RX/TIM1_CH3/OTG_FS_ID/DCMI_D1/EVENTOUT_43") (pintype "bidirectional"))
    )
    (net (code "71") (name "unconnected-(UcA-PA15(JTDI){slash}JTDI{slash}SPI3_NSS{slash}I2S3_WS{slash}TIM2_CH1_ETR{slash}SPI1_NSS{slash}EVENTOUT-Pad50)") (class "Default")
      (node (ref "Uc") (pin "50") (pinfunction "PA15(JTDI)/JTDI/SPI3_NSS/I2S3_WS/TIM2_CH1_ETR/SPI1_NSS/EVENTOUT_50") (pintype "bidirectional"))
    )
    (net (code "72") (name "unconnected-(UcA-PB1{slash}TIM3_CH4{slash}TIM8_CH3N{slash}OTG_HS_ULPI_D2{slash}ETH_MII_RXD3{slash}OTG_HS_INTN{slash}TIM1_CH3N{slash}EVENTOUT{slash}ADC12_IN9-Pad27)") (class "Default")
      (node (ref "Uc") (pin "27") (pinfunction "PB1/TIM3_CH4/TIM8_CH3N/OTG_HS_ULPI_D2/ETH_MII_RXD3/OTG_HS_INTN/TIM1_CH3N/EVENTOUT/ADC12_IN9_27") (pintype "bidirectional"))
    )
    (net (code "73") (name "unconnected-(UcA-PB2-BOOT1(PB2){slash}EVENTOUT-Pad28)") (class "Default")
      (node (ref "Uc") (pin "28") (pinfunction "PB2-BOOT1(PB2)/EVENTOUT_28") (pintype "bidirectional"))
    )
    (net (code "74") (name "unconnected-(UcA-PB8{slash}TIM4_CH3{slash}SDIO_D4{slash}TIM10_CH1{slash}DCMI_D6{slash}ETH_MII_TXD3{slash}I2C1_SCL{slash}CAN1_RX{slash}EVENTOUT-Pad61)") (class "Default")
      (node (ref "Uc") (pin "61") (pinfunction "PB8/TIM4_CH3/SDIO_D4/TIM10_CH1/DCMI_D6/ETH_MII_TXD3/I2C1_SCL/CAN1_RX/EVENTOUT_61") (pintype "bidirectional"))
    )
    (net (code "75") (name "unconnected-(UcA-PB9{slash}SPI2_NSS{slash}I2S2_WS{slash}TIM4_CH4{slash}TIM11_CH1{slash}SDIO_D5{slash}DCMI_D7{slash}I2C1_SDA{slash}CAN1_TX{slash}EVENTOUT-Pad62)") (class "Default")
      (node (ref "Uc") (pin "62") (pinfunction "PB9/SPI2_NSS/I2S2_WS/TIM4_CH4/TIM11_CH1/SDIO_D5/DCMI_D7/I2C1_SDA/CAN1_TX/EVENTOUT_62") (pintype "bidirectional"))
    )
    (net (code "76") (name "unconnected-(UcA-PB12{slash}SPI2_NSS{slash}I2S2_WS{slash}I2C2_SMBA{slash}USART3_CK{slash}TIM1_BKIN{slash}CAN2_RX{slash}OTG_HS_ULPI_D5{slash}ETH_RMII_TXD0{slash}ETH_MII_TXD0{slash}OTG_HS_ID{slash}EVENTOUT-Pad33)") (class "Default")
      (node (ref "Uc") (pin "33") (pinfunction "PB12/SPI2_NSS/I2S2_WS/I2C2_SMBA/USART3_CK/TIM1_BKIN/CAN2_RX/OTG_HS_ULPI_D5/ETH_RMII_TXD0/ETH_MII_TXD0/OTG_HS_ID/EVENTOUT_33") (pintype "bidirectional"))
    )
    (net (code "77") (name "unconnected-(UcA-PB13{slash}SPI2_SCK{slash}I2S2_CK{slash}USART3_CTS{slash}TIM1_CH1N{slash}CAN2_TX{slash}OTG_HS_ULPI_D6{slash}ETH_RMII_TXD1{slash}ETH_MII_TXD1{slash}EVENTOUT{slash}OTG_HS_VBUS-Pad34)") (class "Default")
      (node (ref "Uc") (pin "34") (pinfunction "PB13/SPI2_SCK/I2S2_CK/USART3_CTS/TIM1_CH1N/CAN2_TX/OTG_HS_ULPI_D6/ETH_RMII_TXD1/ETH_MII_TXD1/EVENTOUT/OTG_HS_VBUS_34") (pintype "bidirectional"))
    )
    (net (code "78") (name "unconnected-(UcA-PB14{slash}SPI2_MISO{slash}TIM1_CH2N{slash}TIM12_CH1{slash}OTG_HS_DM{slash}USART3_RTS{slash}TIM8_CH2N{slash}I2S2ext_SD{slash}EVENTOUT-Pad35)") (class "Default")
      (node (ref "Uc") (pin "35") (pinfunction "PB14/SPI2_MISO/TIM1_CH2N/TIM12_CH1/OTG_HS_DM/USART3_RTS/TIM8_CH2N/I2S2ext_SD/EVENTOUT_35") (pintype "bidirectional"))
    )
    (net (code "79") (name "unconnected-(UcA-PB15{slash}SPI2_MOSI{slash}I2S2_SD{slash}TIM1_CH3N{slash}TIM8_CH3N{slash}TIM12_CH2{slash}OTG_HS_DP{slash}EVENTOUT-Pad36)") (class "Default")
      (node (ref "Uc") (pin "36") (pinfunction "PB15/SPI2_MOSI/I2S2_SD/TIM1_CH3N/TIM8_CH3N/TIM12_CH2/OTG_HS_DP/EVENTOUT_36") (pintype "bidirectional"))
    )
    (net (code "80") (name "unconnected-(UcB-PC0{slash}OTG_HS_ULPI_STP{slash}EVENTOUT{slash}ADC123_IN10-Pad8)") (class "Default")
      (node (ref "Uc") (pin "8") (pinfunction "PC0/OTG_HS_ULPI_STP/EVENTOUT/ADC123_IN10_8") (pintype "bidirectional"))
    )
    (net (code "81") (name "unconnected-(UcB-PC1{slash}ETH_MDC{slash}EVENTOUT{slash}ADC123_IN11-Pad9)") (class "Default")
      (node (ref "Uc") (pin "9") (pinfunction "PC1/ETH_MDC/EVENTOUT/ADC123_IN11_9") (pintype "bidirectional"))
    )
    (net (code "82") (name "unconnected-(UcB-PC2{slash}SPI2_MISO{slash}OTG_HS_ULPI_DIR{slash}TH_MII_TXD2{slash}I2S2ext_SD{slash}EVENTOUT{slash}ADC123_IN12-Pad10)") (class "Default")
      (node (ref "Uc") (pin "10") (pinfunction "PC2/SPI2_MISO/OTG_HS_ULPI_DIR/TH_MII_TXD2/I2S2ext_SD/EVENTOUT/ADC123_IN12_10") (pintype "bidirectional"))
    )
    (net (code "83") (name "unconnected-(UcB-PC3{slash}SPI2_MOSI{slash}I2S2_SD{slash}OTG_HS_ULPI_NXT{slash}ETH_MII_TX_CLK{slash}EVENTOUT{slash}ADC123_IN13-Pad11)") (class "Default")
      (node (ref "Uc") (pin "11") (pinfunction "PC3/SPI2_MOSI/I2S2_SD/OTG_HS_ULPI_NXT/ETH_MII_TX_CLK/EVENTOUT/ADC123_IN13_11") (pintype "bidirectional"))
    )
    (net (code "84") (name "unconnected-(UcB-PC4{slash}ETH_RMII_RX_D0{slash}ETH_MII_RX_D0{slash}EVENTOUT{slash}ADC12_IN14-Pad24)") (class "Default")
      (node (ref "Uc") (pin "24") (pinfunction "PC4/ETH_RMII_RX_D0/ETH_MII_RX_D0/EVENTOUT/ADC12_IN14_24") (pintype "bidirectional"))
    )
    (net (code "85") (name "unconnected-(UcB-PC5{slash}ETH_RMII_RX_D1{slash}ETH_MII_RX_D1{slash}EVENTOUT{slash}ADC12_IN15-Pad25)") (class "Default")
      (node (ref "Uc") (pin "25") (pinfunction "PC5/ETH_RMII_RX_D1/ETH_MII_RX_D1/EVENTOUT/ADC12_IN15_25") (pintype "bidirectional"))
    )
    (net (code "86") (name "unconnected-(UcB-PC8{slash}TIM8_CH3{slash}SDIO_D0{slash}TIM3_CH3{slash}USART6_CK{slash}DCMI_D2{slash}EVENTOUT-Pad39)") (class "Default")
      (node (ref "Uc") (pin "39") (pinfunction "PC8/TIM8_CH3/SDIO_D0/TIM3_CH3/USART6_CK/DCMI_D2/EVENTOUT_39") (pintype "bidirectional"))
    )
    (net (code "87") (name "unconnected-(UcB-PC9{slash}I2S_CKIN{slash}MCO2{slash}TIM8_CH4{slash}SDIO_D1{slash}{slash}I2C3_SDA{slash}DCMI_D3{slash}TIM3_CH4{slash}EVENTOUT-Pad40)") (class "Default")
      (node (ref "Uc") (pin "40") (pinfunction "PC9/I2S_CKIN/MCO2/TIM8_CH4/SDIO_D1//I2C3_SDA/DCMI_D3/TIM3_CH4/EVENTOUT_40") (pintype "bidirectional"))
    )
    (net (code "88") (name "unconnected-(UcB-PC10{slash}SPI3_SCK{slash}I2S3_CK{slash}UART4_TX{slash}SDIO_D2{slash}DCMI_D8{slash}USART3_TX{slash}EVENTOUT-Pad51)") (class "Default")
      (node (ref "Uc") (pin "51") (pinfunction "PC10/SPI3_SCK/I2S3_CK/UART4_TX/SDIO_D2/DCMI_D8/USART3_TX/EVENTOUT_51") (pintype "bidirectional"))
    )
    (net (code "89") (name "unconnected-(UcB-PC11{slash}UART4_RX{slash}SPI3_MISO{slash}SDIO_D3{slash}DCMI_D4{slash}USART3_RX{slash}I2S3ext_SD{slash}EVENTOUT-Pad52)") (class "Default")
      (node (ref "Uc") (pin "52") (pinfunction "PC11/UART4_RX/SPI3_MISO/SDIO_D3/DCMI_D4/USART3_RX/I2S3ext_SD/EVENTOUT_52") (pintype "bidirectional"))
    )
    (net (code "90") (name "unconnected-(UcB-PC12{slash}UART5_TX{slash}SDIO_CK{slash}DCMI_D9{slash}SPI3_MOSI{slash}I2S3_SD{slash}USART3_CK{slash}EVENTOUT-Pad53)") (class "Default")
      (node (ref "Uc") (pin "53") (pinfunction "PC12/UART5_TX/SDIO_CK/DCMI_D9/SPI3_MOSI/I2S3_SD/USART3_CK/EVENTOUT_53") (pintype "bidirectional"))
    )
    (net (code "91") (name "unconnected-(UcB-PC13{slash}EVENTOUT{slash}RTC_AF1-Pad2)") (class "Default")
      (node (ref "Uc") (pin "2") (pinfunction "PC13/EVENTOUT/RTC_AF1_2") (pintype "bidirectional"))
    )
    (net (code "92") (name "unconnected-(UcB-PC14-OSC32_IN(PC14){slash}EVENTOUT{slash}OSC32_IN-Pad3)") (class "Default")
      (node (ref "Uc") (pin "3") (pinfunction "PC14-OSC32_IN(PC14)/EVENTOUT/OSC32_IN_3") (pintype "bidirectional"))
    )
    (net (code "93") (name "unconnected-(UcB-PC15-OSC32_OUT(PC15){slash}EVENTOUT{slash}OSC32_OUT-Pad4)") (class "Default")
      (node (ref "Uc") (pin "4") (pinfunction "PC15-OSC32_OUT(PC15)/EVENTOUT/OSC32_OUT_4") (pintype "bidirectional"))
    )
    (net (code "94") (name "unconnected-(UcB-PD2{slash}TIM3_ETR{slash}UART5_RX{slash}SDIO_CMD{slash}DCMI_D11{slash}EVENTOUT-Pad54)") (class "Default")
      (node (ref "Uc") (pin "54") (pinfunction "PD2/TIM3_ETR/UART5_RX/SDIO_CMD/DCMI_D11/EVENTOUT_54") (pintype "bidirectional"))
    )
  )
)
